# LEDs_Buttons.net
KiCad netlist of a schematic drawn in Altium Designer
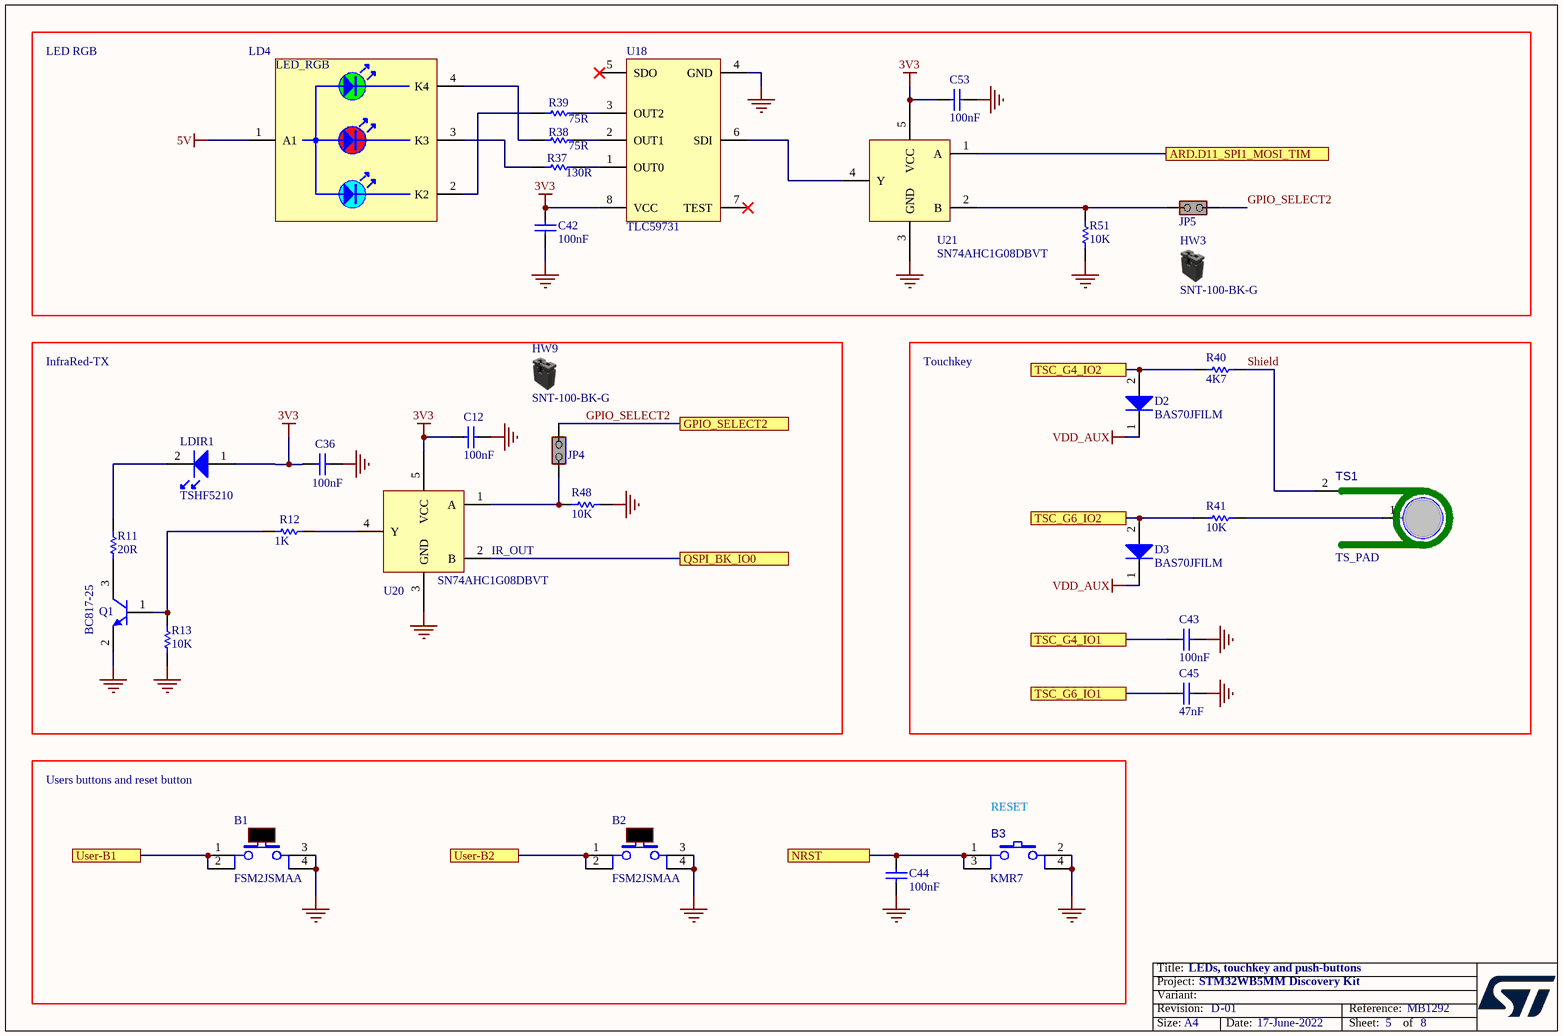
[diagram p0: LEDs_Buttons.SchDoc]

(export (version "E")
  (design (tool "Eeschema 10.0.6"))
  (components
    (comp (ref "B1")
      (value "FSM2JSMAA")
      (footprint "SWI_TE_FSM2JSMAA_WHITE")
      (description "Tactile SWITCH  SPST .05A 24V")
      (fields
        (field (name "INTERNAL_PART_NUMBER") "MCD-02280")
        (field (name "MANUFACTURER") "TE CONNECTIVITY")
      )
      (libsource (lib "MCD_PARTS_database") (part "FSM2JSMAA"))
    )
    (comp (ref "B2")
      (value "FSM2JSMAA")
      (footprint "SWI_TE_FSM2JSMAA_WHITE")
      (description "Tactile SWITCH  SPST .05A 24V")
      (fields
        (field (name "INTERNAL_PART_NUMBER") "MCD-02280")
        (field (name "MANUFACTURER") "TE CONNECTIVITY")
      )
      (libsource (lib "MCD_PARTS_database") (part "FSM2JSMAA"))
    )
    (comp (ref "B3")
      (value "KMR7")
      (footprint "SWI_C&K_KMR721NG-LFS")
      (description "Microminiature SMT Top, 2N, N.O., IP67")
      (fields
        (field (name "INTERNAL_PART_NUMBER") "MCD-01510")
        (field (name "MANUFACTURER_PART_NUMBER") "KMR721NG LFS")
      )
      (libsource (lib "MCD_PARTS_database") (part "SW-PUSH-CMS_KMR_NG"))
    )
    (comp (ref "C12")
      (value "100nF")
      (footprint "C0402")
      (description "Capacitor, MLCC, 100nF, 16V, X7R, +/-10%, 0402, T=0.5mm")
      (fields
        (field (name "INTERNAL_PART_NUMBER") "MCD-00006")
        (field (name "MANUFACTURER_PART_NUMBER") "CC0402KRX7R7BB104")
      )
      (libsource (lib "MCD_PARTS_database") (part "Capacitor"))
    )
    (comp (ref "C36")
      (value "100nF")
      (footprint "C0402")
      (description "Capacitor, MLCC, 100nF, 16V, X7R, +/-10%, 0402, T=0.5mm")
      (fields
        (field (name "INTERNAL_PART_NUMBER") "MCD-00006")
        (field (name "MANUFACTURER_PART_NUMBER") "CC0402KRX7R7BB104")
      )
      (libsource (lib "MCD_PARTS_database") (part "Capacitor"))
    )
    (comp (ref "C42")
      (value "100nF")
      (footprint "C0402")
      (description "Capacitor, MLCC, 100nF, 16V, X7R, +/-10%, 0402, T=0.5mm")
      (fields
        (field (name "INTERNAL_PART_NUMBER") "MCD-00006")
        (field (name "MANUFACTURER_PART_NUMBER") "CC0402KRX7R7BB104")
      )
      (libsource (lib "MCD_PARTS_database") (part "Capacitor"))
    )
    (comp (ref "C43")
      (value "100nF")
      (footprint "C1206_H1P6")
      (description "Capacitor, COG, 100nF, 25V , 1206, 5%")
      (fields
        (field (name "INTERNAL_PART_NUMBER") "MCD-02039")
        (field (name "MANUFACTURER_PART_NUMBER") "C1206X104J3GACTU")
      )
      (libsource (lib "MCD_PARTS_database") (part "Capacitor"))
    )
    (comp (ref "C44")
      (value "100nF")
      (footprint "C0402")
      (description "Capacitor, MLCC, 100nF, 16V, X7R, +/-10%, 0402, T=0.5mm")
      (fields
        (field (name "INTERNAL_PART_NUMBER") "MCD-00006")
        (field (name "MANUFACTURER_PART_NUMBER") "CC0402KRX7R7BB104")
      )
      (libsource (lib "MCD_PARTS_database") (part "Capacitor"))
    )
    (comp (ref "C45")
      (value "47nF")
      (footprint "C0805_KEMET_IPC-7351_DENSITY-LEVEL-B_H1P25")
      (description "Capacitor, MLCC, 47nF, 25V,COG, +/- 5%, 0805, T=1.25 mm")
      (fields (field (name "INTERNAL_PART_NUMBER") "MCD-02040") (field (name "MANUFACTURER") "KEMET"))
      (libsource (lib "MCD_PARTS_database") (part "Capacitor"))
    )
    (comp (ref "C53")
      (value "100nF")
      (footprint "C0402")
      (description "Capacitor, MLCC, 100nF, 16V, X7R, +/-10%, 0402, T=0.5mm")
      (fields
        (field (name "INTERNAL_PART_NUMBER") "MCD-00006")
        (field (name "MANUFACTURER_PART_NUMBER") "CC0402KRX7R7BB104")
      )
      (libsource (lib "MCD_PARTS_database") (part "Capacitor"))
    )
    (comp (ref "D2")
      (value "BAS70JFILM")
      (footprint "DIO_SOD323_1K_2A")
      (description "ultrafast and RF switching diode, VF = 0.41 V @ IF = 1mA; VR = 70V;")
      (fields
        (field (name "INTERNAL_PART_NUMBER") "MCD-01880")
        (field (name "MANUFACTURER") "STMICROELECTRONICS")
      )
      (libsource (lib "MCD_PARTS_database") (part "DIODE_1K_2A"))
    )
    (comp (ref "D3")
      (value "BAS70JFILM")
      (footprint "DIO_SOD323_1K_2A")
      (description "ultrafast and RF switching diode, VF = 0.41 V @ IF = 1mA; VR = 70V;")
      (fields
        (field (name "INTERNAL_PART_NUMBER") "MCD-01880")
        (field (name "MANUFACTURER") "STMICROELECTRONICS")
      )
      (libsource (lib "MCD_PARTS_database") (part "DIODE_1K_2A"))
    )
    (comp (ref "HW3")
      (value "SNT-100-BK-G")
      (description "Shunt, 2.54mm, Black, 4.3A, 6.1mm, 5mR")
      (fields (field (name "INTERNAL_PART_NUMBER") "MCD-00122") (field (name "MANUFACTURER") "SAMTEC"))
      (libsource (lib "MCD_PARTS_database") (part "Shunt Black 2.54mm"))
    )
    (comp (ref "HW9")
      (value "SNT-100-BK-G")
      (description "Shunt, 2.54mm, Black, 4.3A, 6.1mm, 5mR")
      (fields (field (name "INTERNAL_PART_NUMBER") "MCD-00122") (field (name "MANUFACTURER") "SAMTEC"))
      (libsource (lib "MCD_PARTS_database") (part "Shunt Black 2.54mm"))
    )
    (comp (ref "JP4")
      (value "Jumper_Header 2x1 Fitted")
      (footprint "CON_SAMTEC_TSW-102-07-G-S")
      (description "Header, 2x1, 2,54mm, VR, TH, Height 5.84mm/2.54mm - Shunt Fitted by default")
      (fields
        (field (name "INTERNAL_PART_NUMBER") "MCD-01904")
        (field (name "MANUFACTURER_PART_NUMBER") "TSW-102-07-G-S")
      )
      (libsource (lib "") (part "Jumper_Header 2x1 Fitted_1"))
    )
    (comp (ref "JP5")
      (value "Jumper_Header 2x1 Fitted")
      (footprint "CON_SAMTEC_TSW-102-07-G-S")
      (description "Header, 2x1, 2,54mm, VR, TH, Height 5.84mm/2.54mm - Shunt Fitted by default")
      (fields
        (field (name "INTERNAL_PART_NUMBER") "MCD-01904")
        (field (name "MANUFACTURER_PART_NUMBER") "TSW-102-07-G-S")
      )
      (libsource (lib "MCD_PARTS_database") (part "Jumper_Header 2x1 Fitted"))
    )
    (comp (ref "LD4")
      (value "LED_RGB")
      (footprint "LED_TRI-RGB_WURTH_150141M173100")
      (description "LED, RGB 2,8x3,2mm")
      (fields
        (field (name "INTERNAL_PART_NUMBER") "MCD-02035")
        (field (name "MANUFACTURER_PART_NUMBER") "150141M173100")
      )
      (libsource (lib "MCD_PARTS_database") (part "LED_RGB"))
    )
    (comp (ref "LDIR1")
      (value "TSHF5210")
      (footprint "LED_INFRARED_VISHAY_TSHF5210_IN-MODE-SMT_BOARD-EDGE_1A2K_P254")
      (description "Diode infrared, 890nm emitting, T-1 3/4, 35,5mmx2.54mm")
      (fields (field (name "INTERNAL_PART_NUMBER") "MCD-02137") (field (name "MANUFACTURER") "VISHAY"))
      (libsource (lib "MCD_PARTS_database") (part "TSHF5210"))
    )
    (comp (ref "Q1")
      (value "BC817-25")
      (footprint "NPN_SOT23")
      (description "Transistor Bipolar NPN, 45V, 500mA, 100MHz, 300mW, SOT23-3")
      (fields
        (field (name "INTERNAL_PART_NUMBER") "MCD-01385")
        (field (name "MANUFACTURER_PART_NUMBER") "BC817-25LT3G")
      )
      (libsource (lib "MCD_PARTS_database") (part "9013-SOT23"))
    )
    (comp (ref "R11")
      (value "20R")
      (footprint "R0603")
      (description "Resistor,20R,0603,1%,1/10W")
      (fields
        (field (name "INTERNAL_PART_NUMBER") "MCD-00345")
        (field (name "MANUFACTURER_PART_NUMBER") "RC0603FR-0720RL")
      )
      (libsource (lib "MCD_PARTS_database") (part "Resistor"))
    )
    (comp (ref "R12")
      (value "1K")
      (footprint "R0402")
      (description "Resistor,1K,0402,1%,1/16W")
      (fields
        (field (name "INTERNAL_PART_NUMBER") "MCD-00061")
        (field (name "MANUFACTURER_PART_NUMBER") "RC0402FR-071KL")
      )
      (libsource (lib "MCD_PARTS_database") (part "Resistor"))
    )
    (comp (ref "R13")
      (value "10K")
      (footprint "R0402")
      (description "Resistor,10K,0402,1%,1/16W")
      (fields
        (field (name "INTERNAL_PART_NUMBER") "MCD-00053")
        (field (name "MANUFACTURER_PART_NUMBER") "RC0402FR-0710KL")
      )
      (libsource (lib "MCD_PARTS_database") (part "Resistor"))
    )
    (comp (ref "R37")
      (value "130R")
      (footprint "R0603")
      (description "Resistor,130R,0603,1%,1/10W")
      (fields
        (field (name "INTERNAL_PART_NUMBER") "MCD-00380")
        (field (name "MANUFACTURER_PART_NUMBER") "RC0603FR-07130RL")
      )
      (libsource (lib "MCD_PARTS_database") (part "Resistor"))
    )
    (comp (ref "R38")
      (value "75R")
      (footprint "R0603")
      (description "Resistor,75R,0603,1%,1/10W")
      (fields
        (field (name "INTERNAL_PART_NUMBER") "MCD-00516")
        (field (name "MANUFACTURER_PART_NUMBER") "RC0603FR-0775RL")
      )
      (libsource (lib "MCD_PARTS_database") (part "Resistor"))
    )
    (comp (ref "R39")
      (value "75R")
      (footprint "R0603")
      (description "Resistor,75R,0603,1%,1/10W")
      (fields
        (field (name "INTERNAL_PART_NUMBER") "MCD-00516")
        (field (name "MANUFACTURER_PART_NUMBER") "RC0603FR-0775RL")
      )
      (libsource (lib "MCD_PARTS_database") (part "Resistor"))
    )
    (comp (ref "R40")
      (value "4K7")
      (footprint "R0603")
      (description "Resistor,4K7,0603,1%,1/10W")
      (fields
        (field (name "INTERNAL_PART_NUMBER") "MCD-00219")
        (field (name "MANUFACTURER_PART_NUMBER") "RC0603FR-074K7L")
      )
      (libsource (lib "MCD_PARTS_database") (part "Resistor"))
    )
    (comp (ref "R41")
      (value "10K")
      (footprint "R0603")
      (description "Resistor,10K,0603,1%,1/10W")
      (fields
        (field (name "INTERNAL_PART_NUMBER") "MCD-00220")
        (field (name "MANUFACTURER_PART_NUMBER") "RC0603FR-0710KL")
      )
      (libsource (lib "MCD_PARTS_database") (part "Resistor"))
    )
    (comp (ref "R48")
      (value "10K")
      (footprint "R0402")
      (description "Resistor,10K,0402,1%,1/16W")
      (fields
        (field (name "INTERNAL_PART_NUMBER") "MCD-00053")
        (field (name "MANUFACTURER_PART_NUMBER") "RC0402FR-0710KL")
      )
      (libsource (lib "MCD_PARTS_database") (part "Resistor"))
    )
    (comp (ref "R51")
      (value "10K")
      (footprint "R0402")
      (description "Resistor,10K,0402,1%,1/16W")
      (fields
        (field (name "INTERNAL_PART_NUMBER") "MCD-00053")
        (field (name "MANUFACTURER_PART_NUMBER") "RC0402FR-0710KL")
      )
      (libsource (lib "MCD_PARTS_database") (part "Resistor"))
    )
    (comp (ref "TS1")
      (value "TS_PAD")
      (footprint "TSB_TOUCH-SENSING-BUTTON_TS-PAD-10_SHIELD-14_2")
      (description "-Touch Sensing button: diameter 10mm min,  active shield diameter 12mm min")
      (fields
        (field (name "INTERNAL_PART_NUMBER") "MCD-02082")
        (field (name "MANUFACTURER_PART_NUMBER") "Touch_sensing_Button")
      )
      (libsource (lib "MCD_PARTS_database") (part "TS_PAD"))
    )
    (comp (ref "U18")
      (value "TLC59731")
      (footprint "ICC_SOIC8_3P91X4P90_P127_H1P75")
      (description "LED, driver for PWM, 4.90 mm × 3.91 mm")
      (fields
        (field (name "INTERNAL_PART_NUMBER") "MCD-02033")
        (field (name "MANUFACTURER") "TEXAS INSTRUMENTS")
      )
      (libsource (lib "MCD_PARTS_database") (part "TLC59731"))
    )
    (comp (ref "U20")
      (value "SN74AHC1G08DBVT")
      (footprint "ICC_SOT23-5L_H1P45")
      (description "Logic AND Gate, 2.90 mm × 1.60 mm")
      (fields
        (field (name "INTERNAL_PART_NUMBER") "MCD-02053")
        (field (name "MANUFACTURER") "TEXAS INSTRUMENTS")
      )
      (libsource (lib "MCD_PARTS_database") (part "SN74AHC1G08DBVT"))
    )
    (comp (ref "U21")
      (value "SN74AHC1G08DBVT")
      (footprint "ICC_SOT23-5L_H1P45")
      (description "Logic AND Gate, 2.90 mm × 1.60 mm")
      (fields
        (field (name "INTERNAL_PART_NUMBER") "MCD-02053")
        (field (name "MANUFACTURER") "TEXAS INSTRUMENTS")
      )
      (libsource (lib "MCD_PARTS_database") (part "SN74AHC1G08DBVT"))
    )
  )
  (nets
    (net (code "1") (name "/ARD.D11_SPI1_MOSI_TIM") (class "Default")
      (node (ref "U21") (pin "1") (pinfunction "A_1") (pintype "passive"))
    )
    (net (code "2") (name "/GPIO_SELECT2") (class "Default")
      (node (ref "JP4") (pin "1") (pinfunction "COMMON_1") (pintype "passive"))
      (node (ref "JP5") (pin "2") (pinfunction "NO_2") (pintype "passive"))
    )
    (net (code "3") (name "/NRST") (class "Default")
      (node (ref "B3") (pin "1") (pinfunction "1_1") (pintype "passive"))
      (node (ref "B3") (pin "3") (pinfunction "3_3") (pintype "passive"))
      (node (ref "C44") (pin "1") (pinfunction "1_1") (pintype "passive"))
    )
    (net (code "4") (name "/QSPI_BK_IO0") (class "Default")
      (node (ref "U20") (pin "2") (pinfunction "B_2") (pintype "passive"))
    )
    (net (code "5") (name "/Shield") (class "Default")
      (node (ref "R40") (pin "2") (pinfunction "2_2") (pintype "passive"))
      (node (ref "TS1") (pin "2") (pinfunction "SHIELD_2") (pintype "passive"))
    )
    (net (code "6") (name "/TSC_G4_IO1") (class "Default")
      (node (ref "C43") (pin "2") (pinfunction "2_2") (pintype "passive"))
    )
    (net (code "7") (name "/TSC_G4_IO2") (class "Default")
      (node (ref "D2") (pin "2") (pinfunction "A_2") (pintype "passive"))
      (node (ref "R40") (pin "1") (pinfunction "1_1") (pintype "passive"))
    )
    (net (code "8") (name "/TSC_G6_IO1") (class "Default")
      (node (ref "C45") (pin "1") (pinfunction "1_1") (pintype "passive"))
    )
    (net (code "9") (name "/TSC_G6_IO2") (class "Default")
      (node (ref "D3") (pin "2") (pinfunction "A_2") (pintype "passive"))
      (node (ref "R41") (pin "1") (pinfunction "1_1") (pintype "passive"))
    )
    (net (code "10") (name "/User-B1") (class "Default")
      (node (ref "B1") (pin "1") (pinfunction "1_1") (pintype "passive"))
      (node (ref "B1") (pin "2") (pinfunction "2_2") (pintype "passive"))
    )
    (net (code "11") (name "/User-B2") (class "Default")
      (node (ref "B2") (pin "1") (pinfunction "1_1") (pintype "passive"))
      (node (ref "B2") (pin "2") (pinfunction "2_2") (pintype "passive"))
    )
    (net (code "12") (name "3V3") (class "Default")
      (node (ref "C12") (pin "2") (pinfunction "2_2") (pintype "passive"))
      (node (ref "C36") (pin "2") (pinfunction "2_2") (pintype "passive"))
      (node (ref "C42") (pin "2") (pinfunction "2_2") (pintype "passive"))
      (node (ref "C53") (pin "2") (pinfunction "2_2") (pintype "passive"))
      (node (ref "LDIR1") (pin "1") (pinfunction "A_1") (pintype "passive"))
      (node (ref "U18") (pin "8") (pinfunction "VCC_8") (pintype "passive"))
      (node (ref "U20") (pin "5") (pinfunction "VCC_5") (pintype "passive"))
      (node (ref "U21") (pin "5") (pinfunction "VCC_5") (pintype "passive"))
    )
    (net (code "13") (name "5V") (class "Default")
      (node (ref "LD4") (pin "1") (pinfunction "A1_1") (pintype "passive"))
    )
    (net (code "14") (name "GND") (class "Default")
      (node (ref "B1") (pin "3") (pinfunction "3_3") (pintype "passive"))
      (node (ref "B1") (pin "4") (pinfunction "4_4") (pintype "passive"))
      (node (ref "B2") (pin "3") (pinfunction "3_3") (pintype "passive"))
      (node (ref "B2") (pin "4") (pinfunction "4_4") (pintype "passive"))
      (node (ref "B3") (pin "2") (pinfunction "2_2") (pintype "passive"))
      (node (ref "B3") (pin "4") (pinfunction "4_4") (pintype "passive"))
      (node (ref "C12") (pin "1") (pinfunction "1_1") (pintype "passive"))
      (node (ref "C36") (pin "1") (pinfunction "1_1") (pintype "passive"))
      (node (ref "C42") (pin "1") (pinfunction "1_1") (pintype "passive"))
      (node (ref "C43") (pin "1") (pinfunction "1_1") (pintype "passive"))
      (node (ref "C44") (pin "2") (pinfunction "2_2") (pintype "passive"))
      (node (ref "C45") (pin "2") (pinfunction "2_2") (pintype "passive"))
      (node (ref "C53") (pin "1") (pinfunction "1_1") (pintype "passive"))
      (node (ref "Q1") (pin "2") (pinfunction "E_2") (pintype "passive"))
      (node (ref "R13") (pin "1") (pinfunction "1_1") (pintype "passive"))
      (node (ref "R48") (pin "2") (pinfunction "2_2") (pintype "passive"))
      (node (ref "R51") (pin "1") (pinfunction "1_1") (pintype "passive"))
      (node (ref "U18") (pin "4") (pinfunction "GND_4") (pintype "passive"))
      (node (ref "U20") (pin "3") (pinfunction "GND_3") (pintype "passive"))
      (node (ref "U21") (pin "3") (pinfunction "GND_3") (pintype "passive"))
    )
    (net (code "15") (name "Net-(JP4-NO)") (class "Default")
      (node (ref "JP4") (pin "2") (pinfunction "NO_2") (pintype "passive"))
      (node (ref "R48") (pin "1") (pinfunction "1_1") (pintype "passive"))
      (node (ref "U20") (pin "1") (pinfunction "A_1") (pintype "passive"))
    )
    (net (code "16") (name "Net-(JP5-COMMON)") (class "Default")
      (node (ref "JP5") (pin "1") (pinfunction "COMMON_1") (pintype "passive"))
      (node (ref "R51") (pin "2") (pinfunction "2_2") (pintype "passive"))
      (node (ref "U21") (pin "2") (pinfunction "B_2") (pintype "passive"))
    )
    (net (code "17") (name "Net-(LD4-K2)") (class "Default")
      (node (ref "LD4") (pin "2") (pinfunction "K2_2") (pintype "passive"))
      (node (ref "R39") (pin "1") (pinfunction "1_1") (pintype "passive"))
    )
    (net (code "18") (name "Net-(LD4-K3)") (class "Default")
      (node (ref "LD4") (pin "3") (pinfunction "K3_3") (pintype "passive"))
      (node (ref "R37") (pin "1") (pinfunction "1_1") (pintype "passive"))
    )
    (net (code "19") (name "Net-(LD4-K4)") (class "Default")
      (node (ref "LD4") (pin "4") (pinfunction "K4_4") (pintype "passive"))
      (node (ref "R38") (pin "1") (pinfunction "1_1") (pintype "passive"))
    )
    (net (code "20") (name "Net-(LDIR1-K)") (class "Default")
      (node (ref "LDIR1") (pin "2") (pinfunction "K_2") (pintype "passive"))
      (node (ref "R11") (pin "1") (pinfunction "1_1") (pintype "passive"))
    )
    (net (code "21") (name "Net-(Q1-B)") (class "Default")
      (node (ref "Q1") (pin "1") (pinfunction "B_1") (pintype "passive"))
      (node (ref "R12") (pin "1") (pinfunction "1_1") (pintype "passive"))
      (node (ref "R13") (pin "2") (pinfunction "2_2") (pintype "passive"))
    )
    (net (code "22") (name "Net-(Q1-C)") (class "Default")
      (node (ref "Q1") (pin "3") (pinfunction "C_3") (pintype "passive"))
      (node (ref "R11") (pin "2") (pinfunction "2_2") (pintype "passive"))
    )
    (net (code "23") (name "Net-(TS1-TKEY)") (class "Default")
      (node (ref "R41") (pin "2") (pinfunction "2_2") (pintype "passive"))
      (node (ref "TS1") (pin "1") (pinfunction "TKEY_1") (pintype "passive"))
    )
    (net (code "24") (name "Net-(U18-OUT0)") (class "Default")
      (node (ref "R37") (pin "2") (pinfunction "2_2") (pintype "passive"))
      (node (ref "U18") (pin "1") (pinfunction "OUT0_1") (pintype "passive"))
    )
    (net (code "25") (name "Net-(U18-OUT1)") (class "Default")
      (node (ref "R38") (pin "2") (pinfunction "2_2") (pintype "passive"))
      (node (ref "U18") (pin "2") (pinfunction "OUT1_2") (pintype "passive"))
    )
    (net (code "26") (name "Net-(U18-OUT2)") (class "Default")
      (node (ref "R39") (pin "2") (pinfunction "2_2") (pintype "passive"))
      (node (ref "U18") (pin "3") (pinfunction "OUT2_3") (pintype "passive"))
    )
    (net (code "27") (name "Net-(U18-SDI)") (class "Default")
      (node (ref "U18") (pin "6") (pinfunction "SDI_6") (pintype "passive"))
      (node (ref "U21") (pin "4") (pinfunction "Y_4") (pintype "passive"))
    )
    (net (code "28") (name "Net-(U20-Y)") (class "Default")
      (node (ref "R12") (pin "2") (pinfunction "2_2") (pintype "passive"))
      (node (ref "U20") (pin "4") (pinfunction "Y_4") (pintype "passive"))
    )
    (net (code "29") (name "VDD_AUX") (class "Default")
      (node (ref "D2") (pin "1") (pinfunction "K_1") (pintype "passive"))
      (node (ref "D3") (pin "1") (pinfunction "K_1") (pintype "passive"))
    )
    (net (code "30") (name "unconnected-(U18-SDO-Pad5)") (class "Default")
      (node (ref "U18") (pin "5") (pinfunction "SDO_5") (pintype "passive+no_connect"))
    )
    (net (code "31") (name "unconnected-(U18-TEST-Pad7)") (class "Default")
      (node (ref "U18") (pin "7") (pinfunction "TEST_7") (pintype "passive+no_connect"))
    )
  )
)
